# digAudio-rcj-tg10da1nslf.net
KiCad netlist of a schematic drawn in EAGLE
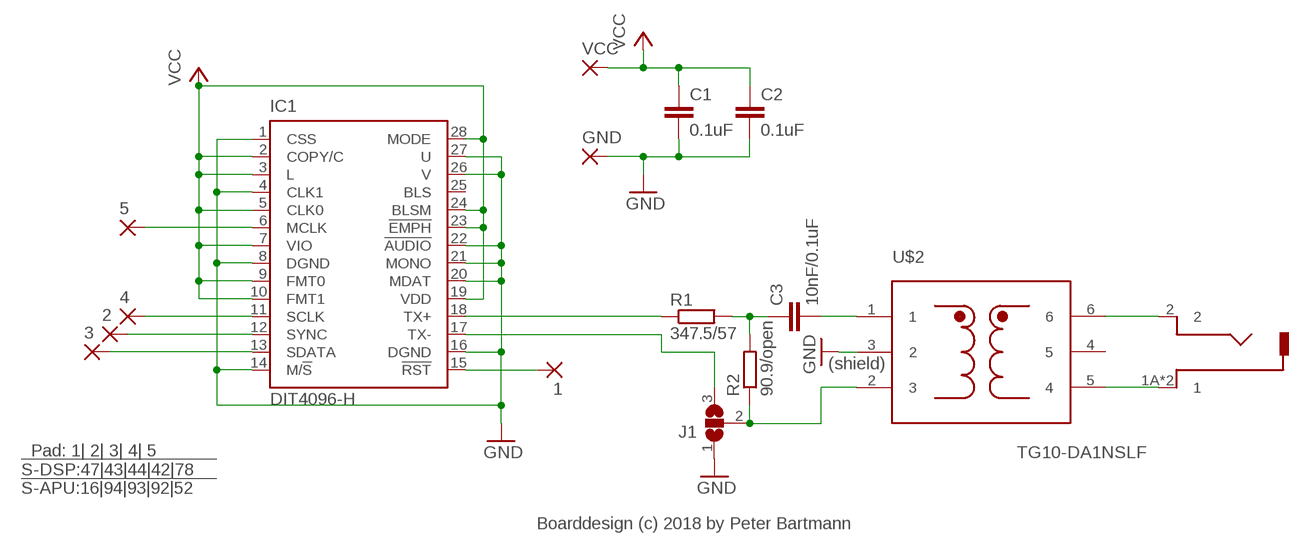
[diagram p0: schematic, sheet 1]

(export (version "E")
  (design (tool "Eeschema 10.0.6"))
  (components
    (comp (ref "1")
      (value "SMD1")
      (footprint "eagle-import:SMD0,8-1,6")
      (libsource (lib "eagle-import") (part "SMD1"))
    )
    (comp (ref "2")
      (value "SMD1")
      (footprint "eagle-import:SMD0,8-1,6")
      (libsource (lib "eagle-import") (part "SMD1"))
    )
    (comp (ref "3")
      (value "SMD1")
      (footprint "eagle-import:SMD0,8-1,6")
      (libsource (lib "eagle-import") (part "SMD1"))
    )
    (comp (ref "4")
      (value "SMD1")
      (footprint "eagle-import:SMD0,8-1,6")
      (libsource (lib "eagle-import") (part "SMD1"))
    )
    (comp (ref "5")
      (value "SMD1")
      (footprint "eagle-import:SMD0,8-1,6")
      (libsource (lib "eagle-import") (part "SMD1"))
    )
    (comp (ref "C1")
      (value "0.1uF")
      (footprint "eagle-import:C0603")
      (libsource (lib "eagle-import") (part "C-EUC0603"))
    )
    (comp (ref "C2")
      (value "0.1uF")
      (footprint "eagle-import:C0603")
      (libsource (lib "eagle-import") (part "C-EUC0603"))
    )
    (comp (ref "C3")
      (value "10nF/0.1uF")
      (footprint "eagle-import:C0603")
      (libsource (lib "eagle-import") (part "C-EUC0603"))
    )
    (comp (ref "GND")
      (value "1,6/0,9")
      (footprint "eagle-import:1,6_0,9")
      (libsource (lib "eagle-import") (part "1,6/0,9"))
    )
    (comp (ref "IC1")
      (value "DIT4096-H")
      (footprint "eagle-import:PW_R-PDSO-G28")
      (fields (field (name "MF") "TEXAS INSTRUMENTS") (field (name "MPN") "DIT4192IPW"))
      (libsource (lib "eagle-import") (part "DIT4192-H"))
    )
    (comp (ref "J1")
      (value "SJ2W")
      (footprint "eagle-import:SJ_2")
      (libsource (lib "eagle-import") (part "SJ2W"))
    )
    (comp (ref "R1")
      (value "347.5/57")
      (footprint "eagle-import:R0603")
      (libsource (lib "eagle-import") (part "R-EU_R0603"))
    )
    (comp (ref "R2")
      (value "90.9/open")
      (footprint "eagle-import:R0603")
      (libsource (lib "eagle-import") (part "R-EU_R0603"))
    )
    (comp (ref "U$1")
      (value "RCJ-013-SMT-TR")
      (footprint "eagle-import:RCJ_01X_SMT_MODIFIED")
      (libsource (lib "eagle-import") (part "RCJ_01X_SMT-MODIFIED"))
    )
    (comp (ref "U$2")
      (value "TG10-DA1NSLF")
      (footprint "eagle-import:TG10-DA1NSFL")
      (libsource (lib "eagle-import") (part "TG10-DA1NSLF"))
    )
    (comp (ref "VCC")
      (value "1,6/0,9")
      (footprint "eagle-import:1,6_0,9")
      (libsource (lib "eagle-import") (part "1,6/0,9"))
    )
  )
  (nets
    (net (code "1") (name "GND") (class "Default")
      (node (ref "C1") (pin "2") (pinfunction "2_2") (pintype "passive"))
      (node (ref "C2") (pin "2") (pinfunction "2_2") (pintype "passive"))
      (node (ref "GND") (pin "1") (pinfunction "P_1") (pintype "passive"))
      (node (ref "IC1") (pin "1") (pinfunction "CSS_1") (pintype "input"))
      (node (ref "IC1") (pin "14") (pinfunction "M/~{S}_14") (pintype "input"))
      (node (ref "IC1") (pin "16") (pinfunction "DGND_16") (pintype "power_in"))
      (node (ref "IC1") (pin "20") (pinfunction "MDAT_20") (pintype "input"))
      (node (ref "IC1") (pin "21") (pinfunction "MONO_21") (pintype "input"))
      (node (ref "IC1") (pin "22") (pinfunction "~{AUDIO}_22") (pintype "input"))
      (node (ref "IC1") (pin "26") (pinfunction "V_26") (pintype "input"))
      (node (ref "IC1") (pin "27") (pinfunction "U_27") (pintype "input"))
      (node (ref "IC1") (pin "4") (pinfunction "CLK1_4") (pintype "input"))
      (node (ref "IC1") (pin "8") (pinfunction "DGND_8") (pintype "power_in"))
      (node (ref "J1") (pin "1") (pinfunction "1_1") (pintype "passive"))
      (node (ref "U$2") (pin "3") (pinfunction "2_3") (pintype "bidirectional"))
    )
    (net (code "2") (name "Net-(1-P)") (class "Default")
      (node (ref "1") (pin "P$1") (pinfunction "P_P$1") (pintype "passive"))
      (node (ref "IC1") (pin "15") (pinfunction "~{RST}_15") (pintype "input"))
    )
    (net (code "3") (name "Net-(2-P)") (class "Default")
      (node (ref "2") (pin "P$1") (pinfunction "P_P$1") (pintype "passive"))
      (node (ref "IC1") (pin "12") (pinfunction "SYNC_12") (pintype "bidirectional"))
    )
    (net (code "4") (name "Net-(3-P)") (class "Default")
      (node (ref "3") (pin "P$1") (pinfunction "P_P$1") (pintype "passive"))
      (node (ref "IC1") (pin "13") (pinfunction "SDATA_13") (pintype "input"))
    )
    (net (code "5") (name "Net-(4-P)") (class "Default")
      (node (ref "4") (pin "P$1") (pinfunction "P_P$1") (pintype "passive"))
      (node (ref "IC1") (pin "11") (pinfunction "SCLK_11") (pintype "bidirectional"))
    )
    (net (code "6") (name "Net-(5-P)") (class "Default")
      (node (ref "5") (pin "P$1") (pinfunction "P_P$1") (pintype "passive"))
      (node (ref "IC1") (pin "6") (pinfunction "MCLK_6") (pintype "input"))
    )
    (net (code "7") (name "Net-(C3-Pad1)") (class "Default")
      (node (ref "C3") (pin "1") (pinfunction "1_1") (pintype "passive"))
      (node (ref "R1") (pin "2") (pinfunction "2_2") (pintype "passive"))
      (node (ref "R2") (pin "2") (pinfunction "2_2") (pintype "passive"))
    )
    (net (code "8") (name "Net-(C3-Pad2)") (class "Default")
      (node (ref "C3") (pin "2") (pinfunction "2_2") (pintype "passive"))
      (node (ref "U$2") (pin "1") (pinfunction "1_1") (pintype "bidirectional"))
    )
    (net (code "9") (name "Net-(IC1-TX+)") (class "Default")
      (node (ref "IC1") (pin "18") (pinfunction "TX+_18") (pintype "output"))
      (node (ref "R1") (pin "1") (pinfunction "1_1") (pintype "passive"))
    )
    (net (code "10") (name "Net-(IC1-TX-)") (class "Default")
      (node (ref "IC1") (pin "17") (pinfunction "TX-_17") (pintype "output"))
      (node (ref "J1") (pin "3") (pinfunction "3_3") (pintype "passive"))
    )
    (net (code "11") (name "Net-(U$1-Pad2)") (class "Default")
      (node (ref "U$1") (pin "2") (pinfunction "2_2") (pintype "bidirectional"))
      (node (ref "U$2") (pin "6") (pinfunction "6_6") (pintype "bidirectional"))
    )
    (net (code "12") (name "Net-(U$2-3)") (class "Default")
      (node (ref "J1") (pin "2") (pinfunction "2_2") (pintype "passive"))
      (node (ref "R2") (pin "1") (pinfunction "1_1") (pintype "passive"))
      (node (ref "U$2") (pin "2") (pinfunction "3_2") (pintype "bidirectional"))
    )
    (net (code "13") (name "Net-(U$2-4)") (class "Default")
      (node (ref "U$1") (pin "1A") (pinfunction "1_1A") (pintype "bidirectional"))
      (node (ref "U$1") (pin "1B") (pinfunction "1_1B") (pintype "bidirectional"))
      (node (ref "U$2") (pin "5") (pinfunction "4_5") (pintype "bidirectional"))
    )
    (net (code "14") (name "VCC") (class "Default")
      (node (ref "C1") (pin "1") (pinfunction "1_1") (pintype "passive"))
      (node (ref "C2") (pin "1") (pinfunction "1_1") (pintype "passive"))
      (node (ref "IC1") (pin "10") (pinfunction "FMT1_10") (pintype "input"))
      (node (ref "IC1") (pin "19") (pinfunction "VDD_19") (pintype "power_in"))
      (node (ref "IC1") (pin "2") (pinfunction "COPY/C_2") (pintype "input"))
      (node (ref "IC1") (pin "23") (pinfunction "~{EMPH}_23") (pintype "input"))
      (node (ref "IC1") (pin "24") (pinfunction "BLSM_24") (pintype "input"))
      (node (ref "IC1") (pin "28") (pinfunction "MODE_28") (pintype "input"))
      (node (ref "IC1") (pin "3") (pinfunction "L_3") (pintype "input"))
      (node (ref "IC1") (pin "5") (pinfunction "CLK0_5") (pintype "input"))
      (node (ref "IC1") (pin "7") (pinfunction "VIO_7") (pintype "power_in"))
      (node (ref "IC1") (pin "9") (pinfunction "FMT0_9") (pintype "input"))
      (node (ref "VCC") (pin "1") (pinfunction "P_1") (pintype "passive"))
    )
    (net (code "15") (name "unconnected-(IC1-BLS-Pad25)") (class "Default")
      (node (ref "IC1") (pin "25") (pinfunction "BLS_25") (pintype "bidirectional"))
    )
    (net (code "16") (name "unconnected-(U$2-5-Pad4)") (class "Default")
      (node (ref "U$2") (pin "4") (pinfunction "5_4") (pintype "bidirectional"))
    )
  )
)
